# Current_measure.net
KiCad netlist of a schematic drawn in Altium Designer
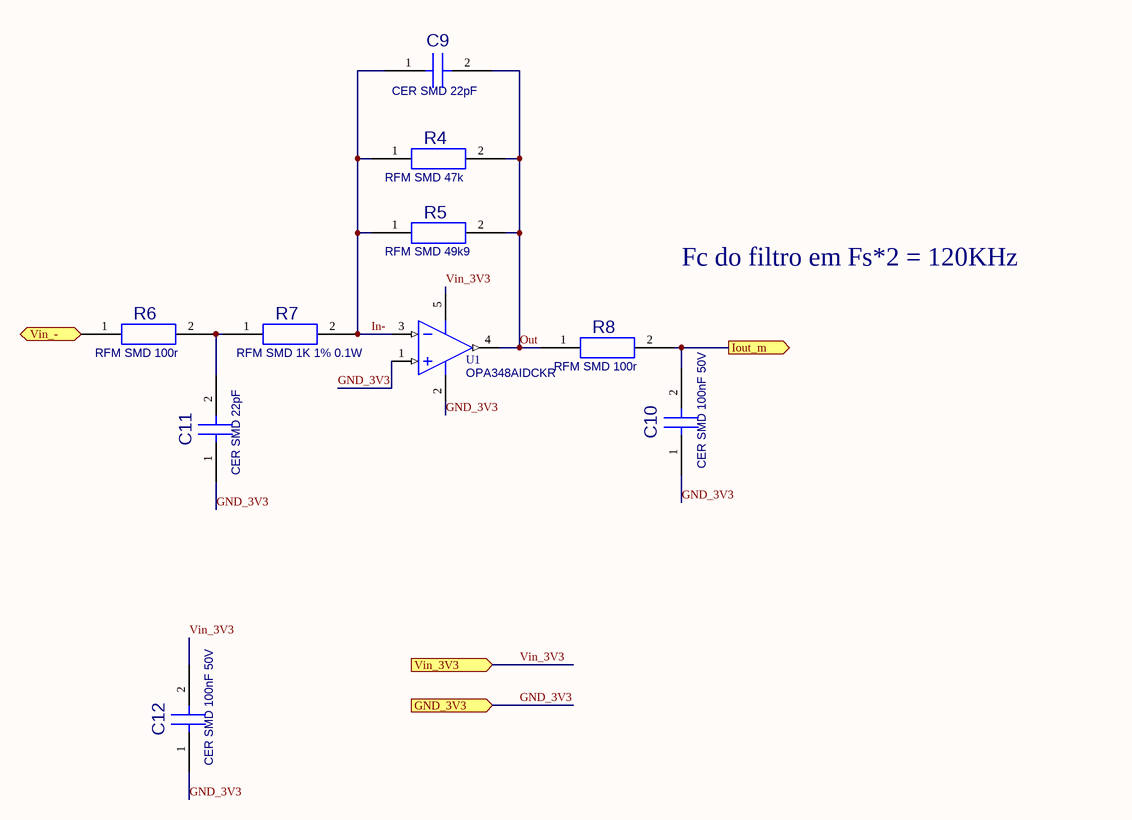
[diagram p0: Current_measure.SchDoc]

(export (version "E")
  (design (tool "Eeschema 10.0.6"))
  (components
    (comp (ref "C9")
      (value "CER SMD 22pF")
      (footprint "C0805_R_V0")
      (fields (field (name "Comment") "10192073"))
      (libsource (lib "Buck_Converter") (part "10192075"))
    )
    (comp (ref "C10")
      (value "CER SMD 100nF 50V")
      (footprint "C0805_R_V0")
      (fields (field (name "Comment") "10192075"))
      (libsource (lib "Buck_Converter") (part "10192075"))
    )
    (comp (ref "C11")
      (value "CER SMD 22pF")
      (footprint "C0805_R_V0")
      (fields (field (name "Comment") "10192073"))
      (libsource (lib "Buck_Converter") (part "10192075"))
    )
    (comp (ref "C12")
      (value "CER SMD 100nF 50V")
      (footprint "C0805_R_V0")
      (fields (field (name "Comment") "10192075"))
      (libsource (lib "Buck_Converter") (part "10192075"))
    )
    (comp (ref "R4")
      (value "RFM SMD 47k")
      (footprint "R0805_R_V0")
      (fields (field (name "Comment") "12314309"))
      (libsource (lib "Buck_Converter") (part "10118077"))
    )
    (comp (ref "R5")
      (value "RFM SMD 49k9")
      (footprint "R0805_R_V0")
      (fields (field (name "Comment") "10192018"))
      (libsource (lib "Buck_Converter") (part "10118077"))
    )
    (comp (ref "R6")
      (value "RFM SMD 100r")
      (footprint "R0805_R_V0")
      (fields (field (name "Comment") "10118083"))
      (libsource (lib "Buck_Converter") (part "10118077"))
    )
    (comp (ref "R7")
      (value "RFM SMD 1K 1% 0.1W")
      (footprint "R0805_R_V0")
      (fields (field (name "Comment") "10118077"))
      (libsource (lib "Buck_Converter") (part "10118077"))
    )
    (comp (ref "R8")
      (value "RFM SMD 100r")
      (footprint "R0805_R_V0")
      (fields (field (name "Comment") "10118083"))
      (libsource (lib "Buck_Converter") (part "10118077"))
    )
    (comp (ref "U1")
      (value "OPA348AIDCKR")
      (footprint "DCK R-PDSO-G5")
      (fields (field (name "MANUFACTURER") "Texas Instruments"))
      (libsource (lib "Buck_Converter") (part "OPA348AIDCKR"))
    )
  )
  (nets
    (net (code "1") (name "/GND_3V3") (class "Default")
      (node (ref "C10") (pin "1") (pinfunction "1_1") (pintype "passive"))
      (node (ref "C11") (pin "1") (pinfunction "1_1") (pintype "passive"))
      (node (ref "C12") (pin "1") (pinfunction "1_1") (pintype "passive"))
      (node (ref "U1") (pin "1") (pinfunction "IN+_1") (pintype "input"))
      (node (ref "U1") (pin "2") (pinfunction "V-_2") (pintype "power_in"))
    )
    (net (code "2") (name "/In-") (class "Default")
      (node (ref "C9") (pin "1") (pinfunction "1_1") (pintype "passive"))
      (node (ref "R4") (pin "1") (pinfunction "1_1") (pintype "passive"))
      (node (ref "R5") (pin "1") (pinfunction "1_1") (pintype "passive"))
      (node (ref "R7") (pin "2") (pinfunction "2_2") (pintype "passive"))
      (node (ref "U1") (pin "3") (pinfunction "IN-_3") (pintype "input"))
    )
    (net (code "3") (name "/Iout_m") (class "Default")
      (node (ref "C10") (pin "2") (pinfunction "2_2") (pintype "passive"))
      (node (ref "R8") (pin "2") (pinfunction "2_2") (pintype "passive"))
    )
    (net (code "4") (name "/Out") (class "Default")
      (node (ref "C9") (pin "2") (pinfunction "2_2") (pintype "passive"))
      (node (ref "R4") (pin "2") (pinfunction "2_2") (pintype "passive"))
      (node (ref "R5") (pin "2") (pinfunction "2_2") (pintype "passive"))
      (node (ref "R8") (pin "1") (pinfunction "1_1") (pintype "passive"))
      (node (ref "U1") (pin "4") (pinfunction "OUT_4") (pintype "output"))
    )
    (net (code "5") (name "/Vin_-") (class "Default")
      (node (ref "R6") (pin "1") (pinfunction "1_1") (pintype "passive"))
    )
    (net (code "6") (name "/Vin_3V3") (class "Default")
      (node (ref "C12") (pin "2") (pinfunction "2_2") (pintype "passive"))
      (node (ref "U1") (pin "5") (pinfunction "V+_5") (pintype "power_in"))
    )
    (net (code "7") (name "Net-(C11-Pad2)") (class "Default")
      (node (ref "C11") (pin "2") (pinfunction "2_2") (pintype "passive"))
      (node (ref "R6") (pin "2") (pinfunction "2_2") (pintype "passive"))
      (node (ref "R7") (pin "1") (pinfunction "1_1") (pintype "passive"))
    )
  )
)
